# GPIO.net
KiCad netlist of a schematic drawn in Altium Designer
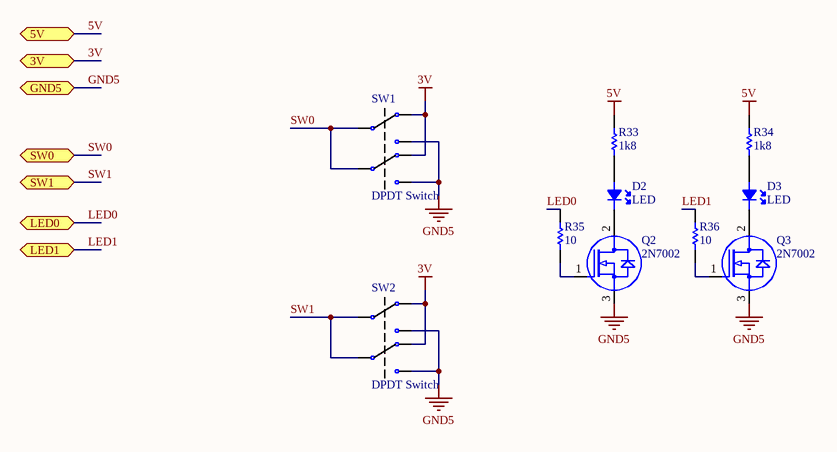
[diagram p0: GPIO.SchDoc]

(export (version "E")
  (design (tool "Eeschema 10.0.6"))
  (components
    (comp (ref "D2") (value "LED") (footprint "dimploma:0805LED") (libsource (lib "diploma") (part "LED")))
    (comp (ref "D3") (value "LED") (footprint "dimploma:0805LED") (libsource (lib "diploma") (part "LED")))
    (comp (ref "Q2")
      (value "2N7002")
      (footprint "dimploma:SOT23")
      (libsource (lib "diploma") (part "2N7002"))
    )
    (comp (ref "Q3")
      (value "2N7002")
      (footprint "dimploma:SOT23")
      (libsource (lib "diploma") (part "2N7002"))
    )
    (comp (ref "R33")
      (value "1k8")
      (footprint "dimploma:0805R")
      (libsource (lib "diploma") (part "RESISTOR"))
    )
    (comp (ref "R34")
      (value "1k8")
      (footprint "dimploma:0805R")
      (libsource (lib "diploma") (part "RESISTOR"))
    )
    (comp (ref "R35") (value "10") (footprint "dimploma:0805R") (libsource (lib "diploma") (part "RESISTOR")))
    (comp (ref "R36") (value "10") (footprint "dimploma:0805R") (libsource (lib "diploma") (part "RESISTOR")))
    (comp (ref "SW1")
      (value "DPDT Switch")
      (footprint "dimploma:DPDT")
      (libsource (lib "diploma") (part "DPDT_Switch"))
    )
    (comp (ref "SW2")
      (value "DPDT Switch")
      (footprint "dimploma:DPDT")
      (libsource (lib "diploma") (part "DPDT_Switch"))
    )
  )
  (nets
    (net (code "1") (name "/LED0") (class "Default")
      (node (ref "R35") (pin "2") (pinfunction "2_2") (pintype "passive"))
    )
    (net (code "2") (name "/LED1") (class "Default")
      (node (ref "R36") (pin "2") (pinfunction "2_2") (pintype "passive"))
    )
    (net (code "3") (name "/SW0") (class "Default")
      (node (ref "SW1") (pin "2") (pinfunction "2_2") (pintype "passive"))
      (node (ref "SW1") (pin "5") (pinfunction "5_5") (pintype "passive"))
    )
    (net (code "4") (name "/SW1") (class "Default")
      (node (ref "SW2") (pin "2") (pinfunction "2_2") (pintype "passive"))
      (node (ref "SW2") (pin "5") (pinfunction "5_5") (pintype "passive"))
    )
    (net (code "5") (name "3V") (class "Default")
      (node (ref "SW1") (pin "1") (pinfunction "1_1") (pintype "passive"))
      (node (ref "SW1") (pin "4") (pinfunction "4_4") (pintype "passive"))
      (node (ref "SW2") (pin "1") (pinfunction "1_1") (pintype "passive"))
      (node (ref "SW2") (pin "4") (pinfunction "4_4") (pintype "passive"))
    )
    (net (code "6") (name "5V") (class "Default")
      (node (ref "R33") (pin "2") (pinfunction "2_2") (pintype "passive"))
      (node (ref "R34") (pin "2") (pinfunction "2_2") (pintype "passive"))
    )
    (net (code "7") (name "GND5") (class "Default")
      (node (ref "Q2") (pin "3") (pinfunction "SOURCE_3") (pintype "passive"))
      (node (ref "Q3") (pin "3") (pinfunction "SOURCE_3") (pintype "passive"))
      (node (ref "SW1") (pin "3") (pinfunction "3_3") (pintype "passive"))
      (node (ref "SW1") (pin "6") (pinfunction "6_6") (pintype "passive"))
      (node (ref "SW2") (pin "3") (pinfunction "3_3") (pintype "passive"))
      (node (ref "SW2") (pin "6") (pinfunction "6_6") (pintype "passive"))
    )
    (net (code "8") (name "Net-(D2-A)") (class "Default")
      (node (ref "D2") (pin "1") (pinfunction "A_1") (pintype "passive"))
      (node (ref "R33") (pin "1") (pinfunction "1_1") (pintype "passive"))
    )
    (net (code "9") (name "Net-(D2-K)") (class "Default")
      (node (ref "D2") (pin "2") (pinfunction "K_2") (pintype "passive"))
      (node (ref "Q2") (pin "2") (pinfunction "DRAIN_2") (pintype "passive"))
    )
    (net (code "10") (name "Net-(D3-A)") (class "Default")
      (node (ref "D3") (pin "1") (pinfunction "A_1") (pintype "passive"))
      (node (ref "R34") (pin "1") (pinfunction "1_1") (pintype "passive"))
    )
    (net (code "11") (name "Net-(D3-K)") (class "Default")
      (node (ref "D3") (pin "2") (pinfunction "K_2") (pintype "passive"))
      (node (ref "Q3") (pin "2") (pinfunction "DRAIN_2") (pintype "passive"))
    )
    (net (code "12") (name "Net-(Q2-GATE)") (class "Default")
      (node (ref "Q2") (pin "1") (pinfunction "GATE_1") (pintype "passive"))
      (node (ref "R35") (pin "1") (pinfunction "1_1") (pintype "passive"))
    )
    (net (code "13") (name "Net-(Q3-GATE)") (class "Default")
      (node (ref "Q3") (pin "1") (pinfunction "GATE_1") (pintype "passive"))
      (node (ref "R36") (pin "1") (pinfunction "1_1") (pintype "passive"))
    )
  )
)
